# MCU.net
KiCad netlist of a schematic drawn in Altium Designer
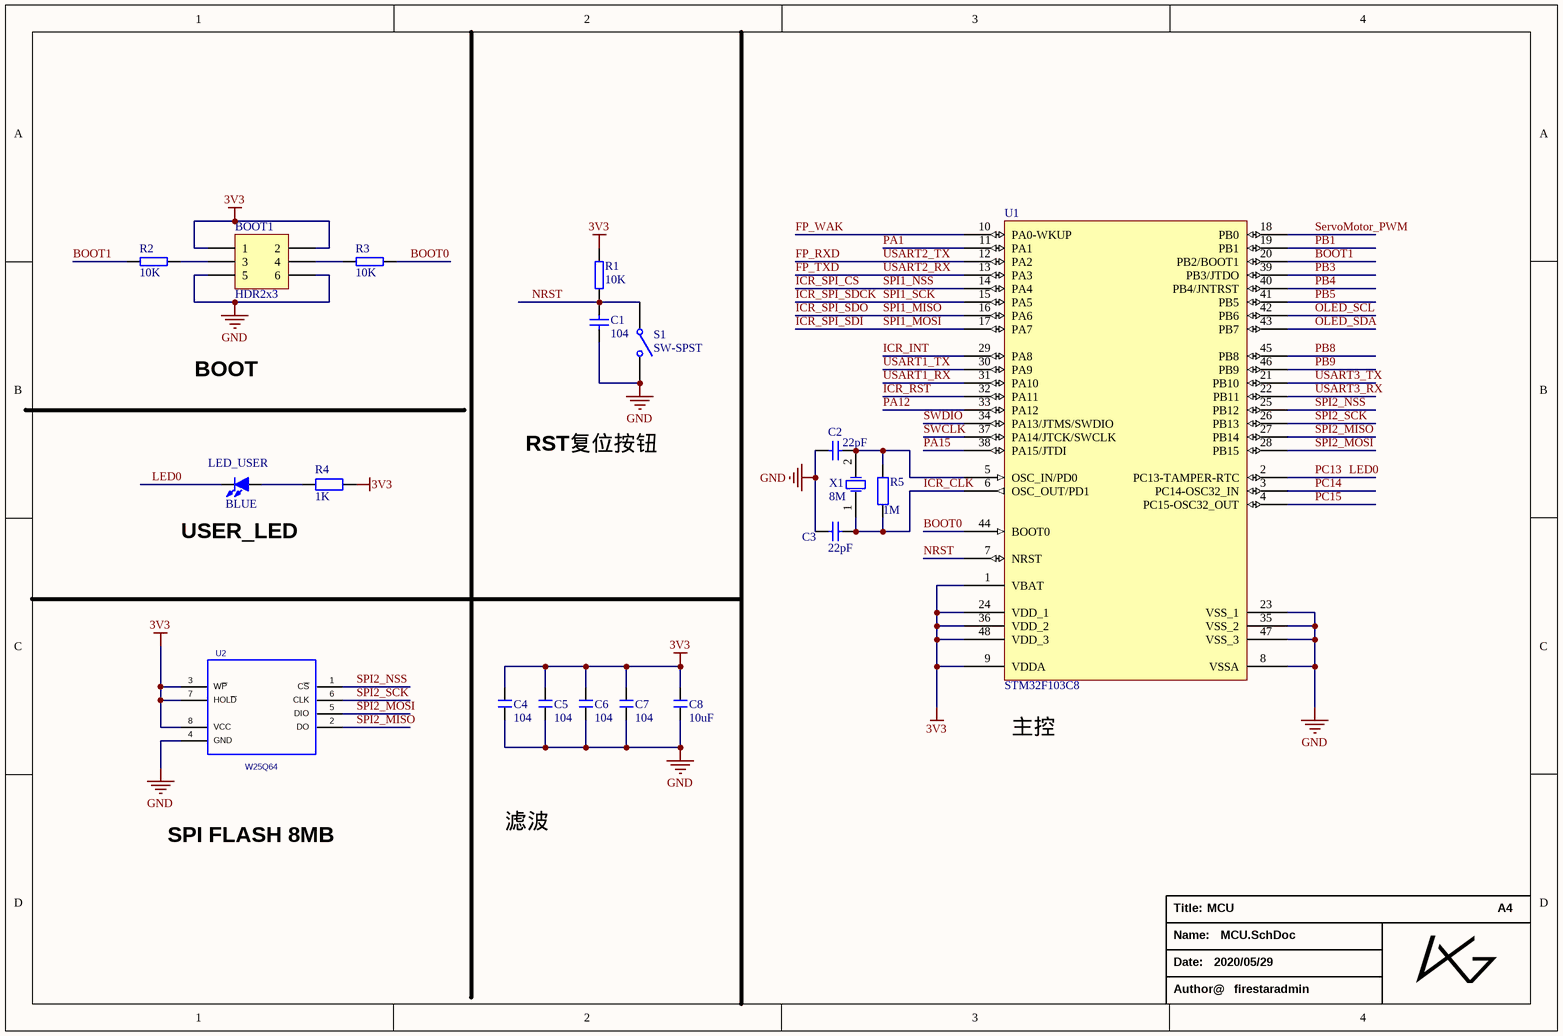
[diagram p0: MCU.SchDoc]

(export (version "E")
  (design (tool "Eeschema 10.0.6"))
  (components
    (comp (ref "BOOT1")
      (value "HDR2x3")
      (footprint "HDR2.54-LI-2x3P")
      (description "Connector")
      (libsource (lib "General") (part "HDR2x3"))
    )
    (comp (ref "C1")
      (value "104")
      (footprint "C 0603_M")
      (description "Capacitor")
      (fields (field (name "PUBLISHER") "ZL_A0OFFICE"))
      (libsource (lib "CommomDevices") (part "CAP1"))
    )
    (comp (ref "C2")
      (value "22pF")
      (footprint "C 0603_M")
      (description "Capacitor")
      (fields (field (name "PUBLISHER") "ZL_A0OFFICE"))
      (libsource (lib "CommomDevices") (part "CAP1"))
    )
    (comp (ref "C3")
      (value "22pF")
      (footprint "C 0603_M")
      (description "Capacitor")
      (fields (field (name "PUBLISHER") "ZL_A0OFFICE"))
      (libsource (lib "CommomDevices") (part "CAP1"))
    )
    (comp (ref "C4")
      (value "104")
      (footprint "C 0603_M")
      (description "无极性贴片电容")
      (fields (field (name "版权归属") "源创客"))
      (libsource (lib "3.1   - 电阻-电容-电感") (part "C"))
    )
    (comp (ref "C5")
      (value "104")
      (footprint "C 0603_M")
      (description "无极性贴片电容")
      (fields (field (name "版权归属") "源创客"))
      (libsource (lib "3.1   - 电阻-电容-电感") (part "C"))
    )
    (comp (ref "C6")
      (value "104")
      (footprint "C 0603_M")
      (description "无极性贴片电容")
      (fields (field (name "版权归属") "源创客"))
      (libsource (lib "3.1   - 电阻-电容-电感") (part "C"))
    )
    (comp (ref "C7")
      (value "104")
      (footprint "C 0603_M")
      (description "无极性贴片电容")
      (fields (field (name "版权归属") "源创客"))
      (libsource (lib "3.1   - 电阻-电容-电感") (part "C"))
    )
    (comp (ref "C8")
      (value "10uF")
      (footprint "C 0805_M")
      (description "无极性贴片电容")
      (fields (field (name "版权归属") "源创客"))
      (libsource (lib "3.1   - 电阻-电容-电感") (part "C"))
    )
    (comp (ref "LED_USER")
      (value "BLUE")
      (footprint "LED 0603B")
      (description "贴片LED")
      (fields (field (name "版权归属") "源创客"))
      (libsource (lib "9.1   - LED") (part "LED-SMD"))
    )
    (comp (ref "R1") (value "10K") (footprint "R 0603_M") (libsource (lib "ZIBO V2.0_Main") (part "R")))
    (comp (ref "R2") (value "10K") (footprint "R 0603_M") (libsource (lib "ZIBO V2.0_Main") (part "R")))
    (comp (ref "R3") (value "10K") (footprint "R 0603_M") (libsource (lib "ZIBO V2.0_Main") (part "R")))
    (comp (ref "R4")
      (value "1K")
      (footprint "R 0805_M")
      (description "贴片电阻")
      (fields (field (name "版权归属") "源创客"))
      (libsource (lib "3.1   - 电阻-电容-电感") (part "R"))
    )
    (comp (ref "R5")
      (value "1M")
      (footprint "R 0603_M")
      (description "贴片电阻")
      (fields (field (name "版权归属") "源创客"))
      (libsource (lib "3.1   - 电阻-电容-电感") (part "R"))
    )
    (comp (ref "S1")
      (value "SW-SPST")
      (footprint "TSW SMD-3*6*2.5")
      (description "Single-Pole, Single-Throw Switch")
      (libsource (lib "Miscellaneous Devices") (part "SW-SPST"))
    )
    (comp (ref "U1")
      (value "STM32F103C8")
      (footprint "LQFP48 7X7_M")
      (description "Flaah:64/RAM:20/IO:36")
      (fields (field (name "版权归属") "源创客"))
      (libsource (lib "2.1   - STM32系列单片机") (part "STM32F103C8"))
    )
    (comp (ref "U2")
      (value "W25Q64")
      (footprint "SOP8W_M")
      (libsource (lib "altium-import") (part "root_0_W25Q64_"))
    )
    (comp (ref "X1")
      (value "8M")
      (footprint "OSC 5032-2P")
      (description "Crystal Oscillator")
      (fields (field (name "PUBLISHER") "ZL_A0OFFICE"))
      (libsource (lib "CommomDevices") (part "XTAL_SMD"))
    )
  )
  (nets
    (net (code "1") (name "/BOOT0") (class "Default")
      (node (ref "R3") (pin "1") (pinfunction "1_1") (pintype "passive"))
      (node (ref "U1") (pin "44") (pinfunction "BOOT0_44") (pintype "input"))
    )
    (net (code "2") (name "/BOOT1") (class "Default")
      (node (ref "R2") (pin "2") (pinfunction "2_2") (pintype "passive"))
      (node (ref "U1") (pin "20") (pinfunction "PB2/BOOT1_20") (pintype "bidirectional"))
    )
    (net (code "3") (name "/FP_RXD") (class "Default")
      (node (ref "U1") (pin "12") (pinfunction "PA2_12") (pintype "bidirectional"))
    )
    (net (code "4") (name "/FP_TXD") (class "Default")
      (node (ref "U1") (pin "13") (pinfunction "PA3_13") (pintype "bidirectional"))
    )
    (net (code "5") (name "/FP_WAK") (class "Default")
      (node (ref "U1") (pin "10") (pinfunction "PA0-WKUP_10") (pintype "bidirectional"))
    )
    (net (code "6") (name "/ICR_CLK") (class "Default")
      (node (ref "C3") (pin "1") (pinfunction "1_1") (pintype "passive"))
      (node (ref "R5") (pin "1") (pinfunction "1_1") (pintype "passive"))
      (node (ref "U1") (pin "6") (pinfunction "OSC_OUT/PD1_6") (pintype "output"))
      (node (ref "X1") (pin "1") (pinfunction "1_1") (pintype "passive"))
    )
    (net (code "7") (name "/ICR_INT") (class "Default")
      (node (ref "U1") (pin "29") (pinfunction "PA8_29") (pintype "bidirectional"))
    )
    (net (code "8") (name "/ICR_RST") (class "Default")
      (node (ref "U1") (pin "32") (pinfunction "PA11_32") (pintype "bidirectional"))
    )
    (net (code "9") (name "/ICR_SPI_CS") (class "Default")
      (node (ref "U1") (pin "14") (pinfunction "PA4_14") (pintype "bidirectional"))
    )
    (net (code "10") (name "/ICR_SPI_SDCK") (class "Default")
      (node (ref "U1") (pin "15") (pinfunction "PA5_15") (pintype "bidirectional"))
    )
    (net (code "11") (name "/ICR_SPI_SDI") (class "Default")
      (node (ref "U1") (pin "17") (pinfunction "PA7_17") (pintype "bidirectional"))
    )
    (net (code "12") (name "/ICR_SPI_SDO") (class "Default")
      (node (ref "U1") (pin "16") (pinfunction "PA6_16") (pintype "bidirectional"))
    )
    (net (code "13") (name "/LED0") (class "Default")
      (node (ref "LED_USER") (pin "2") (pinfunction "K_2") (pintype "passive"))
      (node (ref "U1") (pin "2") (pinfunction "PC13-TAMPER-RTC_2") (pintype "bidirectional"))
    )
    (net (code "14") (name "/NRST") (class "Default")
      (node (ref "C1") (pin "1") (pinfunction "1_1") (pintype "passive"))
      (node (ref "R1") (pin "1") (pinfunction "1_1") (pintype "passive"))
      (node (ref "S1") (pin "1") (pinfunction "COMMON_1") (pintype "passive"))
      (node (ref "U1") (pin "7") (pinfunction "NRST_7") (pintype "bidirectional"))
    )
    (net (code "15") (name "/OLED_SCL") (class "Default")
      (node (ref "U1") (pin "42") (pinfunction "PB6_42") (pintype "bidirectional"))
    )
    (net (code "16") (name "/OLED_SDA") (class "Default")
      (node (ref "U1") (pin "43") (pinfunction "PB7_43") (pintype "bidirectional"))
    )
    (net (code "17") (name "/PA1") (class "Default")
      (node (ref "U1") (pin "11") (pinfunction "PA1_11") (pintype "bidirectional"))
    )
    (net (code "18") (name "/PA12") (class "Default")
      (node (ref "U1") (pin "33") (pinfunction "PA12_33") (pintype "bidirectional"))
    )
    (net (code "19") (name "/PA15") (class "Default")
      (node (ref "U1") (pin "38") (pinfunction "PA15/JTDI_38") (pintype "bidirectional"))
    )
    (net (code "20") (name "/PB1") (class "Default")
      (node (ref "U1") (pin "19") (pinfunction "PB1_19") (pintype "bidirectional"))
    )
    (net (code "21") (name "/PB3") (class "Default")
      (node (ref "U1") (pin "39") (pinfunction "PB3/JTDO_39") (pintype "bidirectional"))
    )
    (net (code "22") (name "/PB4") (class "Default")
      (node (ref "U1") (pin "40") (pinfunction "PB4/JNTRST_40") (pintype "bidirectional"))
    )
    (net (code "23") (name "/PB5") (class "Default")
      (node (ref "U1") (pin "41") (pinfunction "PB5_41") (pintype "bidirectional"))
    )
    (net (code "24") (name "/PB8") (class "Default")
      (node (ref "U1") (pin "45") (pinfunction "PB8_45") (pintype "bidirectional"))
    )
    (net (code "25") (name "/PB9") (class "Default")
      (node (ref "U1") (pin "46") (pinfunction "PB9_46") (pintype "bidirectional"))
    )
    (net (code "26") (name "/PC14") (class "Default")
      (node (ref "U1") (pin "3") (pinfunction "PC14-OSC32_IN_3") (pintype "bidirectional"))
    )
    (net (code "27") (name "/PC15") (class "Default")
      (node (ref "U1") (pin "4") (pinfunction "PC15-OSC32_OUT_4") (pintype "bidirectional"))
    )
    (net (code "28") (name "/SPI2_MISO") (class "Default")
      (node (ref "U1") (pin "27") (pinfunction "PB14_27") (pintype "bidirectional"))
      (node (ref "U2") (pin "2") (pinfunction "DO_2") (pintype "passive"))
    )
    (net (code "29") (name "/SPI2_MOSI") (class "Default")
      (node (ref "U1") (pin "28") (pinfunction "PB15_28") (pintype "bidirectional"))
      (node (ref "U2") (pin "5") (pinfunction "DIO_5") (pintype "passive"))
    )
    (net (code "30") (name "/SPI2_NSS") (class "Default")
      (node (ref "U1") (pin "25") (pinfunction "PB12_25") (pintype "bidirectional"))
      (node (ref "U2") (pin "1") (pinfunction "C~{S}_1") (pintype "passive"))
    )
    (net (code "31") (name "/SPI2_SCK") (class "Default")
      (node (ref "U1") (pin "26") (pinfunction "PB13_26") (pintype "bidirectional"))
      (node (ref "U2") (pin "6") (pinfunction "CLK_6") (pintype "passive"))
    )
    (net (code "32") (name "/SWCLK") (class "Default")
      (node (ref "U1") (pin "37") (pinfunction "PA14/JTCK/SWCLK_37") (pintype "bidirectional"))
    )
    (net (code "33") (name "/SWDIO") (class "Default")
      (node (ref "U1") (pin "34") (pinfunction "PA13/JTMS/SWDIO_34") (pintype "bidirectional"))
    )
    (net (code "34") (name "/ServoMotor_PWM") (class "Default")
      (node (ref "U1") (pin "18") (pinfunction "PB0_18") (pintype "bidirectional"))
    )
    (net (code "35") (name "/USART1_RX") (class "Default")
      (node (ref "U1") (pin "31") (pinfunction "PA10_31") (pintype "bidirectional"))
    )
    (net (code "36") (name "/USART1_TX") (class "Default")
      (node (ref "U1") (pin "30") (pinfunction "PA9_30") (pintype "bidirectional"))
    )
    (net (code "37") (name "/USART3_RX") (class "Default")
      (node (ref "U1") (pin "22") (pinfunction "PB11_22") (pintype "bidirectional"))
    )
    (net (code "38") (name "/USART3_TX") (class "Default")
      (node (ref "U1") (pin "21") (pinfunction "PB10_21") (pintype "bidirectional"))
    )
    (net (code "39") (name "3V3") (class "Default")
      (node (ref "BOOT1") (pin "1") (pinfunction "1_1") (pintype "passive"))
      (node (ref "BOOT1") (pin "2") (pinfunction "2_2") (pintype "passive"))
      (node (ref "C4") (pin "2") (pinfunction "2_2") (pintype "passive"))
      (node (ref "C5") (pin "2") (pinfunction "2_2") (pintype "passive"))
      (node (ref "C6") (pin "2") (pinfunction "2_2") (pintype "passive"))
      (node (ref "C7") (pin "2") (pinfunction "2_2") (pintype "passive"))
      (node (ref "C8") (pin "2") (pinfunction "2_2") (pintype "passive"))
      (node (ref "R1") (pin "2") (pinfunction "2_2") (pintype "passive"))
      (node (ref "R4") (pin "2") (pinfunction "2_2") (pintype "passive"))
      (node (ref "U1") (pin "1") (pinfunction "VBAT_1") (pintype "power_in"))
      (node (ref "U1") (pin "24") (pinfunction "VDD_1_24") (pintype "power_in"))
      (node (ref "U1") (pin "36") (pinfunction "VDD_2_36") (pintype "power_in"))
      (node (ref "U1") (pin "48") (pinfunction "VDD_3_48") (pintype "power_in"))
      (node (ref "U1") (pin "9") (pinfunction "VDDA_9") (pintype "power_in"))
      (node (ref "U2") (pin "3") (pinfunction "W~{P}_3") (pintype "passive"))
      (node (ref "U2") (pin "7") (pinfunction "HOL~{D}_7") (pintype "passive"))
      (node (ref "U2") (pin "8") (pinfunction "VCC_8") (pintype "passive"))
    )
    (net (code "40") (name "GND") (class "Default")
      (node (ref "BOOT1") (pin "5") (pinfunction "5_5") (pintype "passive"))
      (node (ref "BOOT1") (pin "6") (pinfunction "6_6") (pintype "passive"))
      (node (ref "C1") (pin "2") (pinfunction "2_2") (pintype "passive"))
      (node (ref "C2") (pin "2") (pinfunction "2_2") (pintype "passive"))
      (node (ref "C3") (pin "2") (pinfunction "2_2") (pintype "passive"))
      (node (ref "C4") (pin "1") (pinfunction "1_1") (pintype "passive"))
      (node (ref "C5") (pin "1") (pinfunction "1_1") (pintype "passive"))
      (node (ref "C6") (pin "1") (pinfunction "1_1") (pintype "passive"))
      (node (ref "C7") (pin "1") (pinfunction "1_1") (pintype "passive"))
      (node (ref "C8") (pin "1") (pinfunction "1_1") (pintype "passive"))
      (node (ref "S1") (pin "2") (pinfunction "NO_2") (pintype "passive"))
      (node (ref "U1") (pin "23") (pinfunction "VSS_1_23") (pintype "power_in"))
      (node (ref "U1") (pin "35") (pinfunction "VSS_2_35") (pintype "power_in"))
      (node (ref "U1") (pin "47") (pinfunction "VSS_3_47") (pintype "power_in"))
      (node (ref "U1") (pin "8") (pinfunction "VSSA_8") (pintype "power_in"))
      (node (ref "U2") (pin "4") (pinfunction "GND_4") (pintype "passive"))
    )
    (net (code "41") (name "Net-(BOOT1-Pad3)") (class "Default")
      (node (ref "BOOT1") (pin "3") (pinfunction "3_3") (pintype "passive"))
      (node (ref "R2") (pin "1") (pinfunction "1_1") (pintype "passive"))
    )
    (net (code "42") (name "Net-(BOOT1-Pad4)") (class "Default")
      (node (ref "BOOT1") (pin "4") (pinfunction "4_4") (pintype "passive"))
      (node (ref "R3") (pin "2") (pinfunction "2_2") (pintype "passive"))
    )
    (net (code "43") (name "Net-(LED_USER-A)") (class "Default")
      (node (ref "LED_USER") (pin "1") (pinfunction "A_1") (pintype "passive"))
      (node (ref "R4") (pin "1") (pinfunction "1_1") (pintype "passive"))
    )
    (net (code "44") (name "Net-(U1-OSC_IN{slash}PD0)") (class "Default")
      (node (ref "C2") (pin "1") (pinfunction "1_1") (pintype "passive"))
      (node (ref "R5") (pin "2") (pinfunction "2_2") (pintype "passive"))
      (node (ref "U1") (pin "5") (pinfunction "OSC_IN/PD0_5") (pintype "input"))
      (node (ref "X1") (pin "2") (pinfunction "2_2") (pintype "passive"))
    )
  )
)
